# HEBreakoutrev3.net
KiCad netlist of a schematic drawn in EAGLE
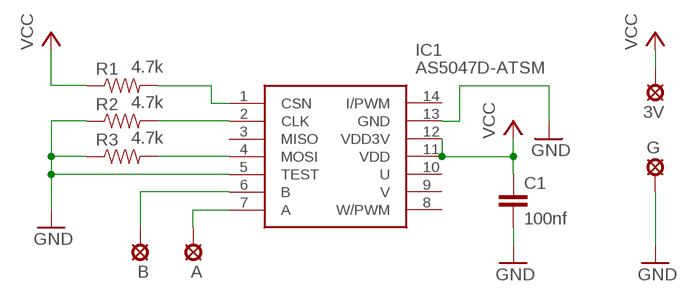
[diagram p0: schematic, sheet 1]

(export (version "E")
  (design (tool "Eeschema 10.0.6"))
  (components
    (comp (ref "3V")
      (value "LSP10")
      (footprint "eagle-import:LSP10")
      (libsource (lib "eagle-import") (part "LSP10"))
    )
    (comp (ref "A")
      (value "LSP10")
      (footprint "eagle-import:LSP10")
      (libsource (lib "eagle-import") (part "LSP10"))
    )
    (comp (ref "B")
      (value "LSP10")
      (footprint "eagle-import:LSP10")
      (libsource (lib "eagle-import") (part "LSP10"))
    )
    (comp (ref "C1")
      (value "100nf")
      (footprint "eagle-import:0603-CAP")
      (libsource (lib "eagle-import") (part "CAP0603-CAP"))
    )
    (comp (ref "G")
      (value "LSP10")
      (footprint "eagle-import:LSP10")
      (libsource (lib "eagle-import") (part "LSP10"))
    )
    (comp (ref "IC1")
      (value "AS5047D-ATSM")
      (footprint "eagle-import:SOP65P640X120-14N")
      (fields (field (name "MOUSER_PART_NUMBER") "985-AS5047D-ATSM"))
      (libsource (lib "eagle-import") (part "AS5047D-ATSM"))
    )
    (comp (ref "R1")
      (value "4.7k")
      (footprint "eagle-import:0603-RES")
      (libsource (lib "eagle-import") (part "RESISTOR0603"))
    )
    (comp (ref "R2")
      (value "4.7k")
      (footprint "eagle-import:0603-RES")
      (libsource (lib "eagle-import") (part "RESISTOR0603"))
    )
    (comp (ref "R3")
      (value "4.7k")
      (footprint "eagle-import:0603-RES")
      (libsource (lib "eagle-import") (part "RESISTOR0603"))
    )
  )
  (nets
    (net (code "1") (name "GND") (class "Default")
      (node (ref "C1") (pin "2") (pinfunction "2_2") (pintype "passive"))
      (node (ref "G") (pin "MP") (pinfunction "MP_MP") (pintype "passive"))
      (node (ref "IC1") (pin "13") (pinfunction "GND_13") (pintype "bidirectional"))
      (node (ref "IC1") (pin "5") (pinfunction "TEST_5") (pintype "bidirectional"))
      (node (ref "R2") (pin "1") (pinfunction "1_1") (pintype "passive"))
      (node (ref "R3") (pin "1") (pinfunction "1_1") (pintype "passive"))
    )
    (net (code "2") (name "Net-(IC1-A)") (class "Default")
      (node (ref "A") (pin "MP") (pinfunction "MP_MP") (pintype "passive"))
      (node (ref "IC1") (pin "7") (pinfunction "A_7") (pintype "bidirectional"))
    )
    (net (code "3") (name "Net-(IC1-B)") (class "Default")
      (node (ref "B") (pin "MP") (pinfunction "MP_MP") (pintype "passive"))
      (node (ref "IC1") (pin "6") (pinfunction "B_6") (pintype "bidirectional"))
    )
    (net (code "4") (name "Net-(IC1-CLK)") (class "Default")
      (node (ref "IC1") (pin "2") (pinfunction "CLK_2") (pintype "bidirectional"))
      (node (ref "R2") (pin "2") (pinfunction "2_2") (pintype "passive"))
    )
    (net (code "5") (name "Net-(IC1-CSN)") (class "Default")
      (node (ref "IC1") (pin "1") (pinfunction "CSN_1") (pintype "bidirectional"))
      (node (ref "R1") (pin "2") (pinfunction "2_2") (pintype "passive"))
    )
    (net (code "6") (name "Net-(IC1-MOSI)") (class "Default")
      (node (ref "IC1") (pin "4") (pinfunction "MOSI_4") (pintype "bidirectional"))
      (node (ref "R3") (pin "2") (pinfunction "2_2") (pintype "passive"))
    )
    (net (code "7") (name "VCC") (class "Default")
      (node (ref "3V") (pin "MP") (pinfunction "MP_MP") (pintype "passive"))
      (node (ref "C1") (pin "1") (pinfunction "1_1") (pintype "passive"))
      (node (ref "IC1") (pin "11") (pinfunction "VDD_11") (pintype "bidirectional"))
      (node (ref "IC1") (pin "12") (pinfunction "VDD3V_12") (pintype "bidirectional"))
      (node (ref "R1") (pin "1") (pinfunction "1_1") (pintype "passive"))
    )
    (net (code "8") (name "unconnected-(IC1-I{slash}PWM-Pad14)") (class "Default")
      (node (ref "IC1") (pin "14") (pinfunction "I/PWM_14") (pintype "bidirectional"))
    )
    (net (code "9") (name "unconnected-(IC1-MISO-Pad3)") (class "Default")
      (node (ref "IC1") (pin "3") (pinfunction "MISO_3") (pintype "bidirectional"))
    )
    (net (code "10") (name "unconnected-(IC1-U-Pad10)") (class "Default")
      (node (ref "IC1") (pin "10") (pinfunction "U_10") (pintype "bidirectional"))
    )
    (net (code "11") (name "unconnected-(IC1-V-Pad9)") (class "Default")
      (node (ref "IC1") (pin "9") (pinfunction "V_9") (pintype "bidirectional"))
    )
    (net (code "12") (name "unconnected-(IC1-W{slash}PWM-Pad8)") (class "Default")
      (node (ref "IC1") (pin "8") (pinfunction "W/PWM_8") (pintype "bidirectional"))
    )
  )
)
